# Speedometer.net
KiCad netlist of a schematic drawn in EAGLE
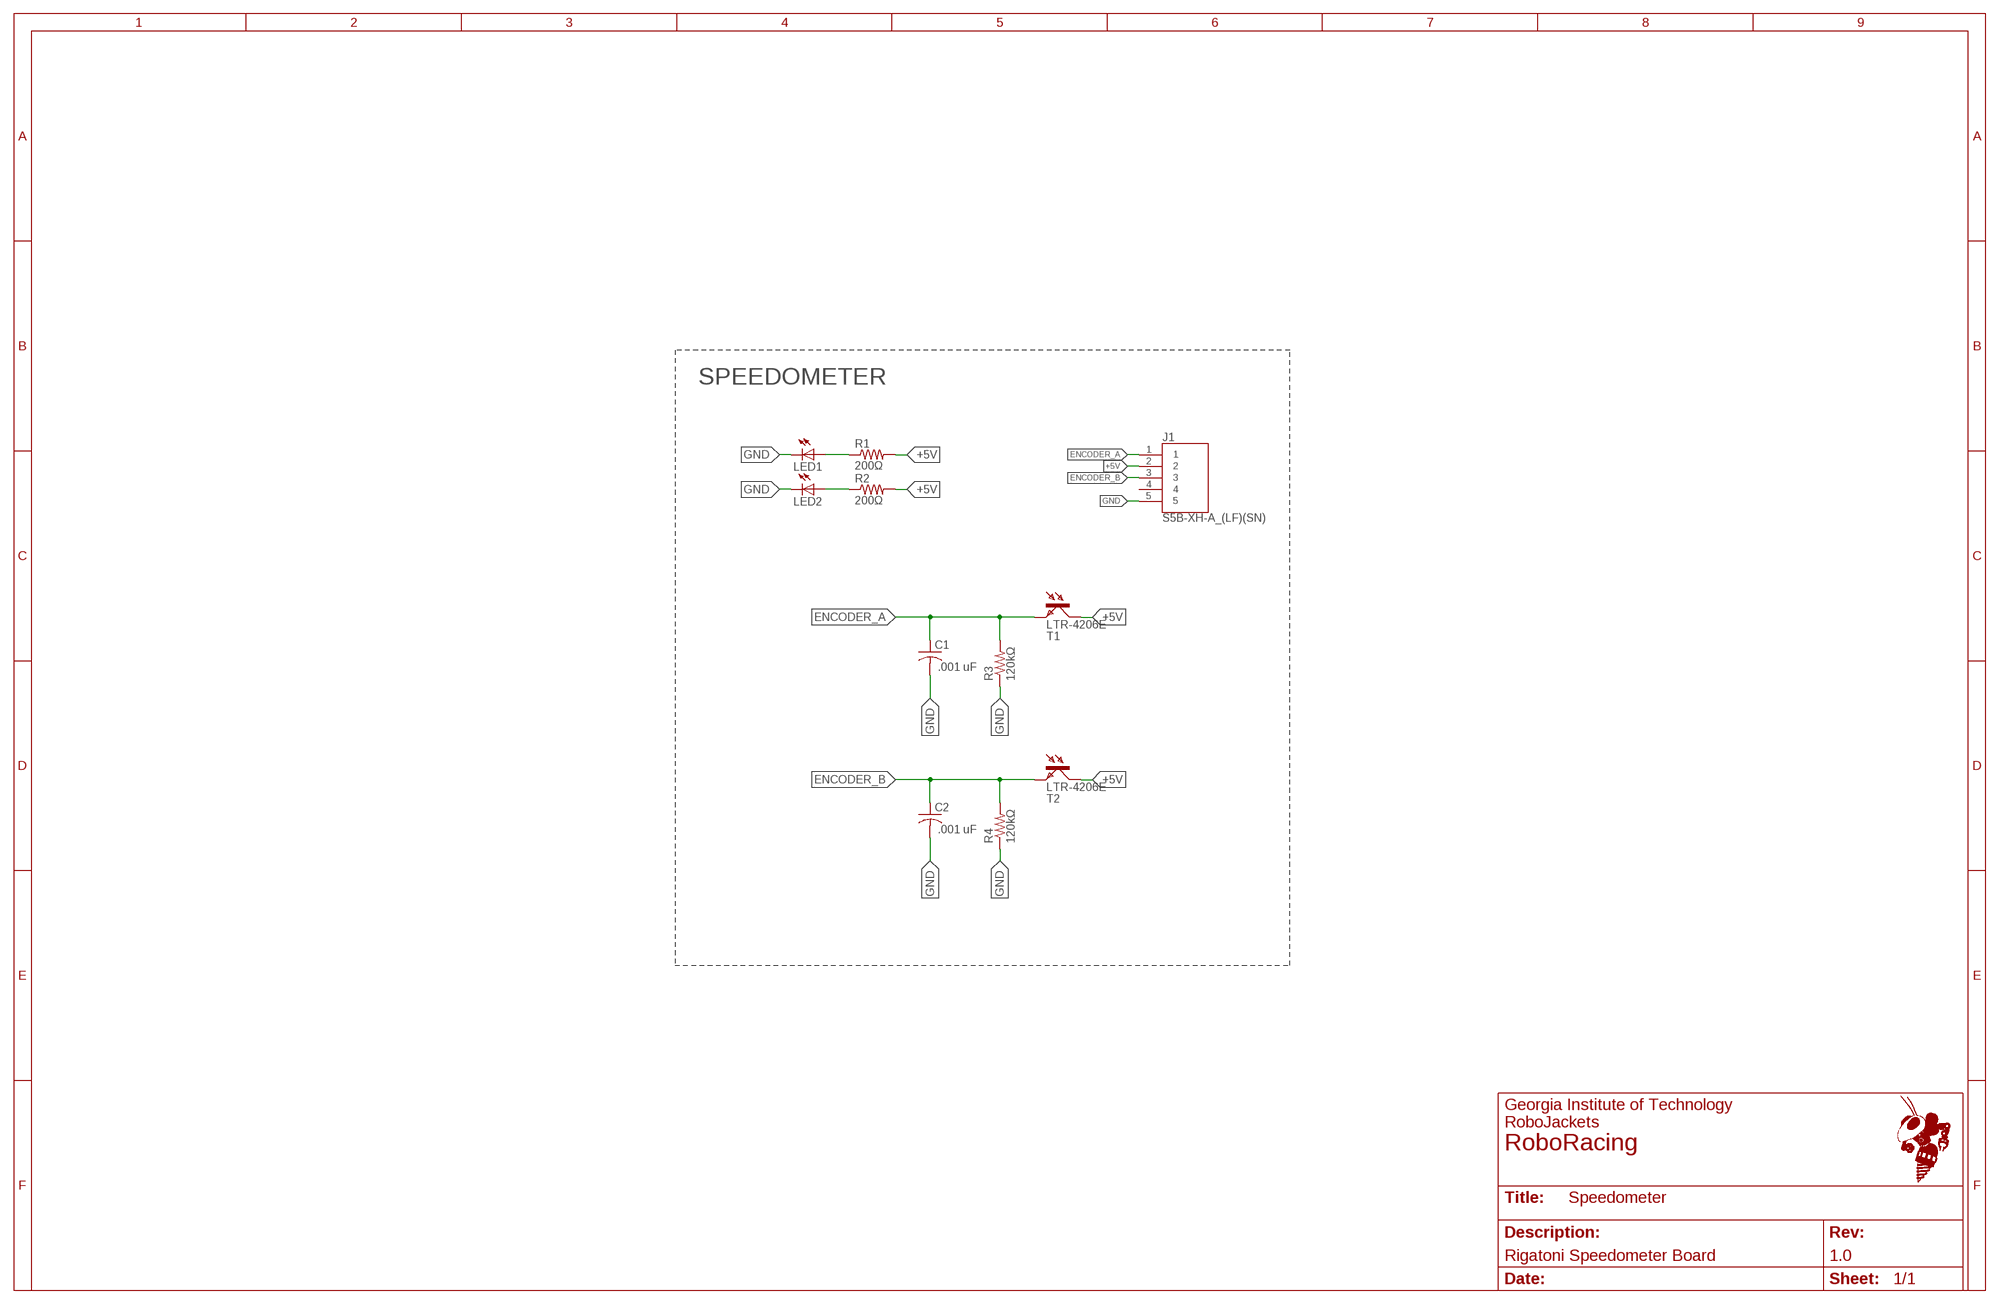
[diagram p0: schematic, sheet 1]

(export (version "E")
  (design (tool "Eeschema 10.0.6"))
  (components
    (comp (ref "C1")
      (value ".001 uF")
      (footprint "eagle-import:C0603")
      (libsource (lib "eagle-import") (part "C-USC0603"))
    )
    (comp (ref "C2")
      (value ".001 uF")
      (footprint "eagle-import:C0603")
      (libsource (lib "eagle-import") (part "C-USC0603"))
    )
    (comp (ref "J1")
      (value "S5B-XH-A_(LF)(SN)")
      (footprint "eagle-import:SHDR5W80P0X250_1X5_1490X1150X6")
      (fields
        (field (name "MANUFACTURER_PART_NUMBER") "S5B-XH-A (LF)(SN)")
        (field (name "RS_PART_NUMBER") "5469072")
      )
      (libsource (lib "eagle-import") (part "S5B-XH-A_(LF)(SN)"))
    )
    (comp (ref "LED1")
      (value "LED3MM")
      (footprint "eagle-import:LED3MM")
      (libsource (lib "eagle-import") (part "LED3MM"))
    )
    (comp (ref "LED2")
      (value "LED3MM")
      (footprint "eagle-import:LED3MM")
      (libsource (lib "eagle-import") (part "LED3MM"))
    )
    (comp (ref "R1")
      (value "200Ω")
      (footprint "eagle-import:R0603")
      (libsource (lib "eagle-import") (part "R-US_R0603"))
    )
    (comp (ref "R2")
      (value "200Ω")
      (footprint "eagle-import:R0603")
      (libsource (lib "eagle-import") (part "R-US_R0603"))
    )
    (comp (ref "R3")
      (value "120kΩ")
      (footprint "eagle-import:R0603")
      (libsource (lib "eagle-import") (part "R-US_R0603"))
    )
    (comp (ref "R4")
      (value "120kΩ")
      (footprint "eagle-import:R0603")
      (libsource (lib "eagle-import") (part "R-US_R0603"))
    )
    (comp (ref "T1")
      (value "LTR-4206E")
      (footprint "eagle-import:BPX81")
      (fields (field (name "MF") "Lite-On Inc."))
      (libsource (lib "eagle-import") (part "LTR-4206E"))
    )
    (comp (ref "T2")
      (value "LTR-4206E")
      (footprint "eagle-import:BPX81")
      (fields (field (name "MF") "Lite-On Inc."))
      (libsource (lib "eagle-import") (part "LTR-4206E"))
    )
  )
  (nets
    (net (code "1") (name "+5V") (class "Default")
      (node (ref "J1") (pin "2") (pinfunction "2_2") (pintype "passive"))
      (node (ref "R1") (pin "2") (pinfunction "2_2") (pintype "passive"))
      (node (ref "R2") (pin "2") (pinfunction "2_2") (pintype "passive"))
      (node (ref "T1") (pin "C") (pinfunction "C_C") (pintype "passive"))
      (node (ref "T2") (pin "C") (pinfunction "C_C") (pintype "passive"))
    )
    (net (code "2") (name "ENCODER_A") (class "Default")
      (node (ref "C1") (pin "1") (pinfunction "1_1") (pintype "passive"))
      (node (ref "J1") (pin "1") (pinfunction "1_1") (pintype "passive"))
      (node (ref "R3") (pin "2") (pinfunction "2_2") (pintype "passive"))
      (node (ref "T1") (pin "E") (pinfunction "E_E") (pintype "passive"))
    )
    (net (code "3") (name "ENCODER_B") (class "Default")
      (node (ref "C2") (pin "1") (pinfunction "1_1") (pintype "passive"))
      (node (ref "J1") (pin "3") (pinfunction "3_3") (pintype "passive"))
      (node (ref "R4") (pin "2") (pinfunction "2_2") (pintype "passive"))
      (node (ref "T2") (pin "E") (pinfunction "E_E") (pintype "passive"))
    )
    (net (code "4") (name "GND") (class "Default")
      (node (ref "C1") (pin "2") (pinfunction "2_2") (pintype "passive"))
      (node (ref "C2") (pin "2") (pinfunction "2_2") (pintype "passive"))
      (node (ref "J1") (pin "5") (pinfunction "5_5") (pintype "passive"))
      (node (ref "LED1") (pin "K") (pinfunction "C_K") (pintype "passive"))
      (node (ref "LED2") (pin "K") (pinfunction "C_K") (pintype "passive"))
      (node (ref "R3") (pin "1") (pinfunction "1_1") (pintype "passive"))
      (node (ref "R4") (pin "1") (pinfunction "1_1") (pintype "passive"))
    )
    (net (code "5") (name "Net-(LED1-PadA)") (class "Default")
      (node (ref "LED1") (pin "A") (pinfunction "A_A") (pintype "passive"))
      (node (ref "R1") (pin "1") (pinfunction "1_1") (pintype "passive"))
    )
    (net (code "6") (name "Net-(LED2-PadA)") (class "Default")
      (node (ref "LED2") (pin "A") (pinfunction "A_A") (pintype "passive"))
      (node (ref "R2") (pin "1") (pinfunction "1_1") (pintype "passive"))
    )
    (net (code "7") (name "unconnected-(J1-Pad4)") (class "Default")
      (node (ref "J1") (pin "4") (pinfunction "4_4") (pintype "passive"))
    )
  )
)
